# POWER_2_2.net
KiCad netlist of a schematic drawn in Altium Designer
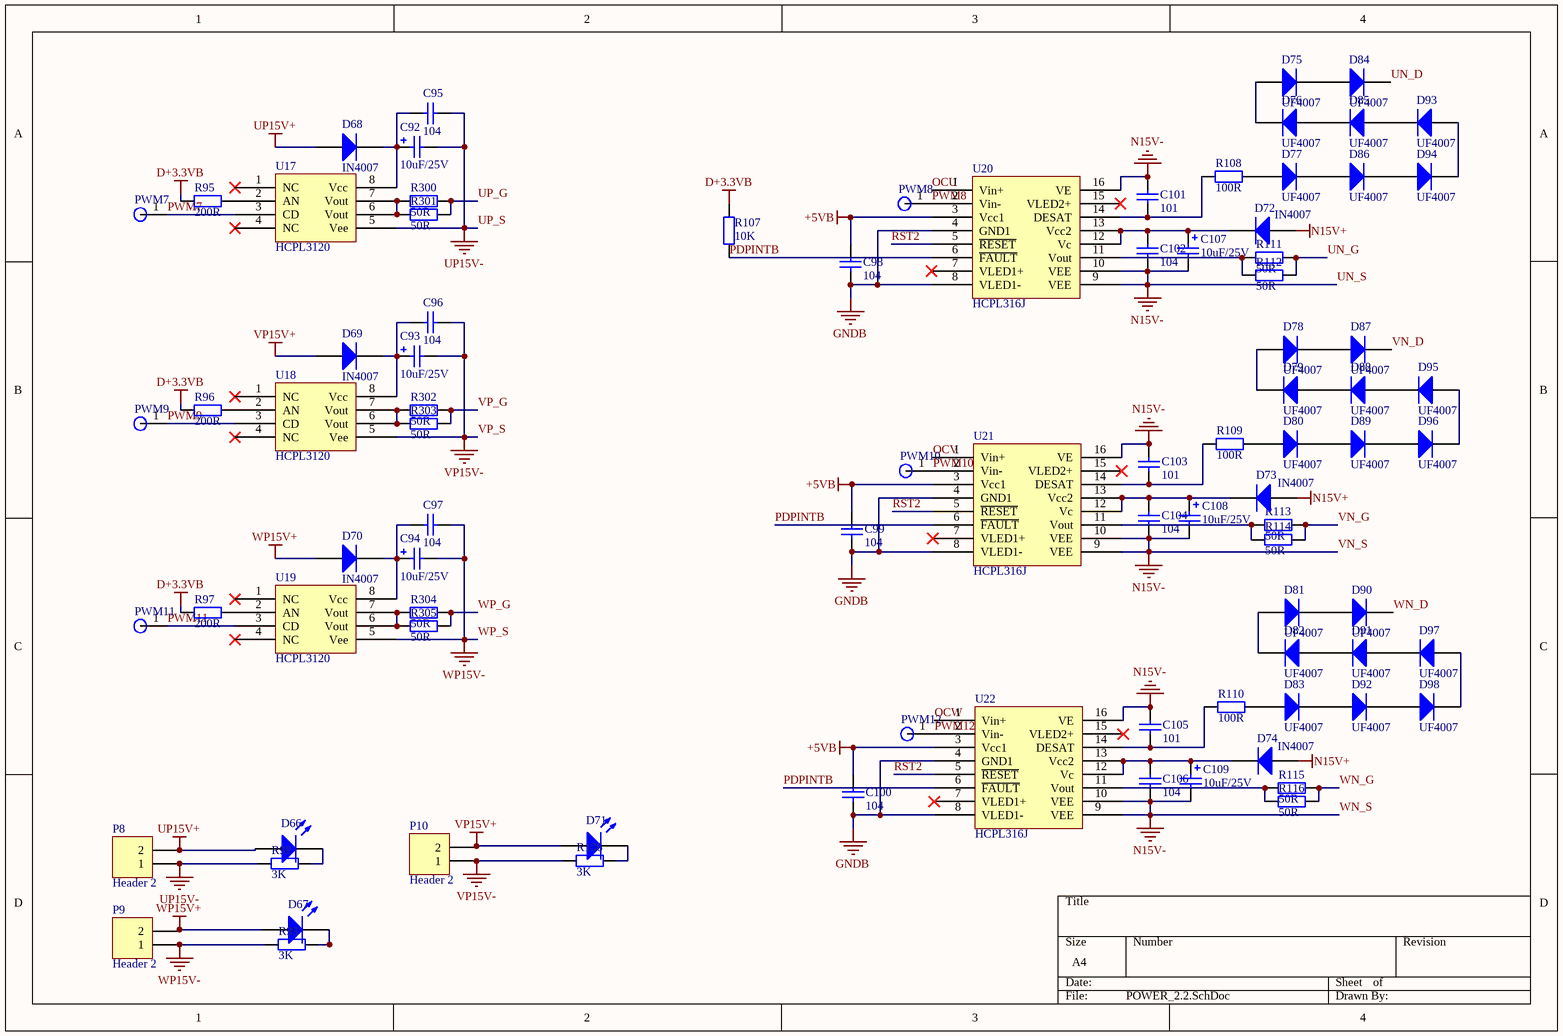
[diagram p0: POWER_2.2.SchDoc]

(export (version "E")
  (design (tool "Eeschema 10.0.6"))
  (components
    (comp (ref "C92")
      (value "10uF/25V")
      (footprint "C_10UF/25V")
      (description "钽电解")
      (libsource (lib "*") (part "Cap tan"))
    )
    (comp (ref "C93")
      (value "10uF/25V")
      (footprint "C_10UF/25V")
      (description "钽电解")
      (libsource (lib "*") (part "Cap tan"))
    )
    (comp (ref "C94")
      (value "10uF/25V")
      (footprint "C_10UF/25V")
      (description "钽电解")
      (libsource (lib "*") (part "Cap tan"))
    )
    (comp (ref "C95")
      (value "104")
      (footprint "C2012-0805")
      (description "普通电容")
      (libsource (lib "Mylib") (part "Cap"))
    )
    (comp (ref "C96")
      (value "104")
      (footprint "C2012-0805")
      (description "普通电容")
      (libsource (lib "Mylib") (part "Cap"))
    )
    (comp (ref "C97")
      (value "104")
      (footprint "C2012-0805")
      (description "普通电容")
      (libsource (lib "Mylib") (part "Cap"))
    )
    (comp (ref "C98")
      (value "104")
      (footprint "C2012-0805")
      (description "普通电容")
      (libsource (lib "*") (part "Cap"))
    )
    (comp (ref "C99")
      (value "104")
      (footprint "C2012-0805")
      (description "普通电容")
      (libsource (lib "*") (part "Cap"))
    )
    (comp (ref "C100")
      (value "104")
      (footprint "C2012-0805")
      (description "普通电容")
      (libsource (lib "*") (part "Cap"))
    )
    (comp (ref "C101")
      (value "101")
      (footprint "Rad-0.2")
      (description "普通电容")
      (libsource (lib "*") (part "Cap"))
    )
    (comp (ref "C102")
      (value "104")
      (footprint "C2012-0805")
      (description "普通电容")
      (libsource (lib "*") (part "Cap"))
    )
    (comp (ref "C103")
      (value "101")
      (footprint "Rad-0.2")
      (description "普通电容")
      (libsource (lib "*") (part "Cap"))
    )
    (comp (ref "C104")
      (value "104")
      (footprint "C2012-0805")
      (description "普通电容")
      (libsource (lib "*") (part "Cap"))
    )
    (comp (ref "C105")
      (value "101")
      (footprint "Rad-0.2")
      (description "普通电容")
      (libsource (lib "*") (part "Cap"))
    )
    (comp (ref "C106")
      (value "104")
      (footprint "C2012-0805")
      (description "普通电容")
      (libsource (lib "*") (part "Cap"))
    )
    (comp (ref "C107")
      (value "10uF/25V")
      (footprint "C_10UF/25V")
      (description "钽电解")
      (libsource (lib "*") (part "Cap tan"))
    )
    (comp (ref "C108")
      (value "10uF/25V")
      (footprint "C_10UF/25V")
      (description "钽电解")
      (libsource (lib "*") (part "Cap tan"))
    )
    (comp (ref "C109")
      (value "10uF/25V")
      (footprint "C_10UF/25V")
      (description "钽电解")
      (libsource (lib "*") (part "Cap tan"))
    )
    (comp (ref "D66") (value "~") (footprint "LED-SMD") (libsource (lib "Mylib") (part "LED")))
    (comp (ref "D67") (value "~") (footprint "LED-SMD") (libsource (lib "Mylib") (part "LED")))
    (comp (ref "D68")
      (value "IN4007")
      (footprint "DIODE4007")
      (description "普通整流二极管")
      (libsource (lib "Mylib") (part "Diode IN4007"))
    )
    (comp (ref "D69")
      (value "IN4007")
      (footprint "DIODE4007")
      (description "普通整流二极管")
      (libsource (lib "Mylib") (part "Diode IN4007"))
    )
    (comp (ref "D70")
      (value "IN4007")
      (footprint "DIODE4007")
      (description "普通整流二极管")
      (libsource (lib "Mylib") (part "Diode IN4007"))
    )
    (comp (ref "D71") (value "~") (footprint "LED-SMD") (libsource (lib "Mylib") (part "LED")))
    (comp (ref "D72")
      (value "IN4007")
      (footprint "DIODE4007")
      (description "普通整流二极管")
      (libsource (lib "*") (part "Diode IN4007"))
    )
    (comp (ref "D73")
      (value "IN4007")
      (footprint "DIODE4007")
      (description "普通整流二极管")
      (libsource (lib "*") (part "Diode IN4007"))
    )
    (comp (ref "D74")
      (value "IN4007")
      (footprint "DIODE4007")
      (description "普通整流二极管")
      (libsource (lib "*") (part "Diode IN4007"))
    )
    (comp (ref "D75")
      (value "UF4007")
      (footprint "DIODE4007")
      (description "普通整流二极管")
      (libsource (lib "*") (part "Diode IN4007"))
    )
    (comp (ref "D76")
      (value "UF4007")
      (footprint "DIODE4007")
      (description "普通整流二极管")
      (libsource (lib "*") (part "Diode IN4007"))
    )
    (comp (ref "D77")
      (value "UF4007")
      (footprint "DIODE4007")
      (description "普通整流二极管")
      (libsource (lib "*") (part "Diode IN4007"))
    )
    (comp (ref "D78")
      (value "UF4007")
      (footprint "DIODE4007")
      (description "普通整流二极管")
      (libsource (lib "*") (part "Diode IN4007"))
    )
    (comp (ref "D79")
      (value "UF4007")
      (footprint "DIODE4007")
      (description "普通整流二极管")
      (libsource (lib "*") (part "Diode IN4007"))
    )
    (comp (ref "D80")
      (value "UF4007")
      (footprint "DIODE4007")
      (description "普通整流二极管")
      (libsource (lib "*") (part "Diode IN4007"))
    )
    (comp (ref "D81")
      (value "UF4007")
      (footprint "DIODE4007")
      (description "普通整流二极管")
      (libsource (lib "*") (part "Diode IN4007"))
    )
    (comp (ref "D82")
      (value "UF4007")
      (footprint "DIODE4007")
      (description "普通整流二极管")
      (libsource (lib "*") (part "Diode IN4007"))
    )
    (comp (ref "D83")
      (value "UF4007")
      (footprint "DIODE4007")
      (description "普通整流二极管")
      (libsource (lib "*") (part "Diode IN4007"))
    )
    (comp (ref "D84")
      (value "UF4007")
      (footprint "DIODE4007")
      (description "普通整流二极管")
      (libsource (lib "*") (part "Diode IN4007"))
    )
    (comp (ref "D85")
      (value "UF4007")
      (footprint "DIODE4007")
      (description "普通整流二极管")
      (libsource (lib "*") (part "Diode IN4007"))
    )
    (comp (ref "D86")
      (value "UF4007")
      (footprint "DIODE4007")
      (description "普通整流二极管")
      (libsource (lib "*") (part "Diode IN4007"))
    )
    (comp (ref "D87")
      (value "UF4007")
      (footprint "DIODE4007")
      (description "普通整流二极管")
      (libsource (lib "*") (part "Diode IN4007"))
    )
    (comp (ref "D88")
      (value "UF4007")
      (footprint "DIODE4007")
      (description "普通整流二极管")
      (libsource (lib "*") (part "Diode IN4007"))
    )
    (comp (ref "D89")
      (value "UF4007")
      (footprint "DIODE4007")
      (description "普通整流二极管")
      (libsource (lib "*") (part "Diode IN4007"))
    )
    (comp (ref "D90")
      (value "UF4007")
      (footprint "DIODE4007")
      (description "普通整流二极管")
      (libsource (lib "*") (part "Diode IN4007"))
    )
    (comp (ref "D91")
      (value "UF4007")
      (footprint "DIODE4007")
      (description "普通整流二极管")
      (libsource (lib "*") (part "Diode IN4007"))
    )
    (comp (ref "D92")
      (value "UF4007")
      (footprint "DIODE4007")
      (description "普通整流二极管")
      (libsource (lib "*") (part "Diode IN4007"))
    )
    (comp (ref "D93")
      (value "UF4007")
      (footprint "DIODE4007")
      (description "普通整流二极管")
      (libsource (lib "*") (part "Diode IN4007"))
    )
    (comp (ref "D94")
      (value "UF4007")
      (footprint "DIODE4007")
      (description "普通整流二极管")
      (libsource (lib "*") (part "Diode IN4007"))
    )
    (comp (ref "D95")
      (value "UF4007")
      (footprint "DIODE4007")
      (description "普通整流二极管")
      (libsource (lib "*") (part "Diode IN4007"))
    )
    (comp (ref "D96")
      (value "UF4007")
      (footprint "DIODE4007")
      (description "普通整流二极管")
      (libsource (lib "*") (part "Diode IN4007"))
    )
    (comp (ref "D97")
      (value "UF4007")
      (footprint "DIODE4007")
      (description "普通整流二极管")
      (libsource (lib "*") (part "Diode IN4007"))
    )
    (comp (ref "D98")
      (value "UF4007")
      (footprint "DIODE4007")
      (description "普通整流二极管")
      (libsource (lib "*") (part "Diode IN4007"))
    )
    (comp (ref "P8")
      (value "Header 2")
      (footprint "HDR1X2")
      (description "Header, 2-Pin")
      (fields (field (name "PUBLISHER") "Altium Limited"))
      (libsource (lib "Miscellaneous Connectors") (part "Header 2"))
    )
    (comp (ref "P9")
      (value "Header 2")
      (footprint "HDR1X2")
      (description "Header, 2-Pin")
      (fields (field (name "PUBLISHER") "Altium Limited"))
      (libsource (lib "Miscellaneous Connectors") (part "Header 2"))
    )
    (comp (ref "P10")
      (value "Header 2")
      (footprint "HDR1X2")
      (description "Header, 2-Pin")
      (fields (field (name "PUBLISHER") "Altium Limited"))
      (libsource (lib "Miscellaneous Connectors") (part "Header 2"))
    )
    (comp (ref "R95") (value "200R") (footprint "R2012-0805") (libsource (lib "*") (part "Res")))
    (comp (ref "R96") (value "200R") (footprint "R2012-0805") (libsource (lib "*") (part "Res")))
    (comp (ref "R97") (value "200R") (footprint "R2012-0805") (libsource (lib "*") (part "Res")))
    (comp (ref "R98") (value "3K") (footprint "R2012-0805") (libsource (lib "") (part "Res_1")))
    (comp (ref "R99") (value "3K") (footprint "R2012-0805") (libsource (lib "") (part "Res_1")))
    (comp (ref "R106") (value "3K") (footprint "R2012-0805") (libsource (lib "") (part "Res_1")))
    (comp (ref "R107") (value "10K") (footprint "R2012-0805") (libsource (lib "") (part "Res_2")))
    (comp (ref "R108") (value "100R") (footprint "R2012-0805") (libsource (lib "*") (part "Res")))
    (comp (ref "R109") (value "100R") (footprint "R2012-0805") (libsource (lib "*") (part "Res")))
    (comp (ref "R110") (value "100R") (footprint "R2012-0805") (libsource (lib "*") (part "Res")))
    (comp (ref "R111") (value "50R") (footprint "R2012-0805") (libsource (lib "*") (part "Res")))
    (comp (ref "R112") (value "50R") (footprint "R2012-0805") (libsource (lib "*") (part "Res")))
    (comp (ref "R113") (value "50R") (footprint "R2012-0805") (libsource (lib "*") (part "Res")))
    (comp (ref "R114") (value "50R") (footprint "R2012-0805") (libsource (lib "*") (part "Res")))
    (comp (ref "R115") (value "50R") (footprint "R2012-0805") (libsource (lib "*") (part "Res")))
    (comp (ref "R116") (value "50R") (footprint "R2012-0805") (libsource (lib "*") (part "Res")))
    (comp (ref "R300") (value "50R") (footprint "R2012-0805") (libsource (lib "*") (part "Res")))
    (comp (ref "R301") (value "50R") (footprint "R2012-0805") (libsource (lib "*") (part "Res")))
    (comp (ref "R302") (value "50R") (footprint "R2012-0805") (libsource (lib "*") (part "Res")))
    (comp (ref "R303") (value "50R") (footprint "R2012-0805") (libsource (lib "*") (part "Res")))
    (comp (ref "R304") (value "50R") (footprint "R2012-0805") (libsource (lib "*") (part "Res")))
    (comp (ref "R305") (value "50R") (footprint "R2012-0805") (libsource (lib "*") (part "Res")))
    (comp (ref "T32") (value "PWM8") (footprint "PIN1") (description "测试脚") (libsource (lib "*") (part "TP")))
    (comp (ref "T33")
      (value "PWM10")
      (footprint "PIN1")
      (description "测试脚")
      (libsource (lib "*") (part "TP"))
    )
    (comp (ref "T34")
      (value "PWM12")
      (footprint "PIN1")
      (description "测试脚")
      (libsource (lib "*") (part "TP"))
    )
    (comp (ref "TP6")
      (value "PWM7")
      (footprint "PIN1")
      (description "测试脚")
      (libsource (lib "Mylib") (part "TP"))
    )
    (comp (ref "TP7")
      (value "PWM9")
      (footprint "PIN1")
      (description "测试脚")
      (libsource (lib "Mylib") (part "TP"))
    )
    (comp (ref "TP8")
      (value "PWM11")
      (footprint "PIN1")
      (description "测试脚")
      (libsource (lib "Mylib") (part "TP"))
    )
    (comp (ref "U17") (value "HCPL3120") (footprint "HCPL3120") (libsource (lib "Mylib") (part "HCPL3120")))
    (comp (ref "U18") (value "HCPL3120") (footprint "HCPL3120") (libsource (lib "Mylib") (part "HCPL3120")))
    (comp (ref "U19") (value "HCPL3120") (footprint "HCPL3120") (libsource (lib "Mylib") (part "HCPL3120")))
    (comp (ref "U20") (value "HCPL316J") (footprint "HCPL316J") (libsource (lib "*") (part "HCPL316J")))
    (comp (ref "U21") (value "HCPL316J") (footprint "HCPL316J") (libsource (lib "*") (part "HCPL316J")))
    (comp (ref "U22") (value "HCPL316J") (footprint "HCPL316J") (libsource (lib "*") (part "HCPL316J")))
  )
  (nets
    (net (code "1") (name "+5VB") (class "Default")
      (node (ref "C100") (pin "2") (pinfunction "2_2") (pintype "passive"))
      (node (ref "C98") (pin "2") (pinfunction "2_2") (pintype "passive"))
      (node (ref "C99") (pin "2") (pinfunction "2_2") (pintype "passive"))
      (node (ref "U20") (pin "3") (pinfunction "Vcc1_3") (pintype "passive"))
      (node (ref "U21") (pin "3") (pinfunction "Vcc1_3") (pintype "passive"))
      (node (ref "U22") (pin "3") (pinfunction "Vcc1_3") (pintype "passive"))
    )
    (net (code "2") (name "/OCU") (class "Default")
      (node (ref "U20") (pin "1") (pinfunction "Vin+_1") (pintype "passive"))
    )
    (net (code "3") (name "/OCV") (class "Default")
      (node (ref "U21") (pin "1") (pinfunction "Vin+_1") (pintype "passive"))
    )
    (net (code "4") (name "/OCW") (class "Default")
      (node (ref "U22") (pin "1") (pinfunction "Vin+_1") (pintype "passive"))
    )
    (net (code "5") (name "/PDPINTB") (class "Default")
      (node (ref "R107") (pin "1") (pinfunction "1_1") (pintype "passive"))
      (node (ref "U20") (pin "6") (pinfunction "~{FAULT}_6") (pintype "passive"))
      (node (ref "U21") (pin "6") (pinfunction "~{FAULT}_6") (pintype "passive"))
      (node (ref "U22") (pin "6") (pinfunction "~{FAULT}_6") (pintype "passive"))
    )
    (net (code "6") (name "/PWM7") (class "Default")
      (node (ref "TP6") (pin "1") (pinfunction "A_1") (pintype "passive"))
      (node (ref "U17") (pin "3") (pinfunction "CD_3") (pintype "passive"))
    )
    (net (code "7") (name "/PWM8") (class "Default")
      (node (ref "T32") (pin "1") (pinfunction "A_1") (pintype "passive"))
      (node (ref "U20") (pin "2") (pinfunction "Vin-_2") (pintype "passive"))
    )
    (net (code "8") (name "/PWM9") (class "Default")
      (node (ref "TP7") (pin "1") (pinfunction "A_1") (pintype "passive"))
      (node (ref "U18") (pin "3") (pinfunction "CD_3") (pintype "passive"))
    )
    (net (code "9") (name "/PWM10") (class "Default")
      (node (ref "T33") (pin "1") (pinfunction "A_1") (pintype "passive"))
      (node (ref "U21") (pin "2") (pinfunction "Vin-_2") (pintype "passive"))
    )
    (net (code "10") (name "/PWM11") (class "Default")
      (node (ref "TP8") (pin "1") (pinfunction "A_1") (pintype "passive"))
      (node (ref "U19") (pin "3") (pinfunction "CD_3") (pintype "passive"))
    )
    (net (code "11") (name "/PWM12") (class "Default")
      (node (ref "T34") (pin "1") (pinfunction "A_1") (pintype "passive"))
      (node (ref "U22") (pin "2") (pinfunction "Vin-_2") (pintype "passive"))
    )
    (net (code "12") (name "/RST2") (class "Default")
      (node (ref "U20") (pin "5") (pinfunction "~{RESET}_5") (pintype "passive"))
      (node (ref "U21") (pin "5") (pinfunction "~{RESET}_5") (pintype "passive"))
      (node (ref "U22") (pin "5") (pinfunction "~{RESET}_5") (pintype "passive"))
    )
    (net (code "13") (name "/UN_D") (class "Default")
      (node (ref "D84") (pin "2") (pinfunction "K_2") (pintype "passive"))
    )
    (net (code "14") (name "/UN_G") (class "Default")
      (node (ref "R111") (pin "1") (pinfunction "1_1") (pintype "passive"))
      (node (ref "R112") (pin "1") (pinfunction "1_1") (pintype "passive"))
    )
    (net (code "15") (name "/UP_G") (class "Default")
      (node (ref "R300") (pin "1") (pinfunction "1_1") (pintype "passive"))
      (node (ref "R301") (pin "1") (pinfunction "1_1") (pintype "passive"))
    )
    (net (code "16") (name "/VN_D") (class "Default")
      (node (ref "D87") (pin "2") (pinfunction "K_2") (pintype "passive"))
    )
    (net (code "17") (name "/VN_G") (class "Default")
      (node (ref "R113") (pin "1") (pinfunction "1_1") (pintype "passive"))
      (node (ref "R114") (pin "1") (pinfunction "1_1") (pintype "passive"))
    )
    (net (code "18") (name "/VP_G") (class "Default")
      (node (ref "R302") (pin "1") (pinfunction "1_1") (pintype "passive"))
      (node (ref "R303") (pin "1") (pinfunction "1_1") (pintype "passive"))
    )
    (net (code "19") (name "/WN_D") (class "Default")
      (node (ref "D90") (pin "2") (pinfunction "K_2") (pintype "passive"))
    )
    (net (code "20") (name "/WN_G") (class "Default")
      (node (ref "R115") (pin "1") (pinfunction "1_1") (pintype "passive"))
      (node (ref "R116") (pin "1") (pinfunction "1_1") (pintype "passive"))
    )
    (net (code "21") (name "/WP_G") (class "Default")
      (node (ref "R304") (pin "1") (pinfunction "1_1") (pintype "passive"))
      (node (ref "R305") (pin "1") (pinfunction "1_1") (pintype "passive"))
    )
    (net (code "22") (name "D+3.3VB") (class "Default")
      (node (ref "R107") (pin "2") (pinfunction "2_2") (pintype "passive"))
      (node (ref "R95") (pin "2") (pinfunction "2_2") (pintype "passive"))
      (node (ref "R96") (pin "2") (pinfunction "2_2") (pintype "passive"))
      (node (ref "R97") (pin "2") (pinfunction "2_2") (pintype "passive"))
    )
    (net (code "23") (name "GNDB") (class "Default")
      (node (ref "C100") (pin "1") (pinfunction "1_1") (pintype "passive"))
      (node (ref "C98") (pin "1") (pinfunction "1_1") (pintype "passive"))
      (node (ref "C99") (pin "1") (pinfunction "1_1") (pintype "passive"))
      (node (ref "U20") (pin "4") (pinfunction "GND1_4") (pintype "passive"))
      (node (ref "U20") (pin "8") (pinfunction "VLED1-_8") (pintype "passive"))
      (node (ref "U21") (pin "4") (pinfunction "GND1_4") (pintype "passive"))
      (node (ref "U21") (pin "8") (pinfunction "VLED1-_8") (pintype "passive"))
      (node (ref "U22") (pin "4") (pinfunction "GND1_4") (pintype "passive"))
      (node (ref "U22") (pin "8") (pinfunction "VLED1-_8") (pintype "passive"))
    )
    (net (code "24") (name "N15V+") (class "Default")
      (node (ref "D72") (pin "1") (pinfunction "A_1") (pintype "passive"))
      (node (ref "D73") (pin "1") (pinfunction "A_1") (pintype "passive"))
      (node (ref "D74") (pin "1") (pinfunction "A_1") (pintype "passive"))
    )
    (net (code "25") (name "N15V-") (class "Default")
      (node (ref "C101") (pin "2") (pinfunction "2_2") (pintype "passive"))
      (node (ref "C102") (pin "1") (pinfunction "1_1") (pintype "passive"))
      (node (ref "C103") (pin "2") (pinfunction "2_2") (pintype "passive"))
      (node (ref "C104") (pin "1") (pinfunction "1_1") (pintype "passive"))
      (node (ref "C105") (pin "2") (pinfunction "2_2") (pintype "passive"))
      (node (ref "C106") (pin "1") (pinfunction "1_1") (pintype "passive"))
      (node (ref "C107") (pin "2") (pinfunction "2_2") (pintype "passive"))
      (node (ref "C108") (pin "2") (pinfunction "2_2") (pintype "passive"))
      (node (ref "C109") (pin "2") (pinfunction "2_2") (pintype "passive"))
      (node (ref "U20") (pin "10") (pinfunction "VEE_10") (pintype "passive"))
      (node (ref "U20") (pin "16") (pinfunction "VE_16") (pintype "passive"))
      (node (ref "U20") (pin "9") (pinfunction "VEE_9") (pintype "passive"))
      (node (ref "U21") (pin "10") (pinfunction "VEE_10") (pintype "passive"))
      (node (ref "U21") (pin "16") (pinfunction "VE_16") (pintype "passive"))
      (node (ref "U21") (pin "9") (pinfunction "VEE_9") (pintype "passive"))
      (node (ref "U22") (pin "10") (pinfunction "VEE_10") (pintype "passive"))
      (node (ref "U22") (pin "16") (pinfunction "VE_16") (pintype "passive"))
      (node (ref "U22") (pin "9") (pinfunction "VEE_9") (pintype "passive"))
    )
    (net (code "26") (name "Net-(D66-K)") (class "Default")
      (node (ref "D66") (pin "2") (pinfunction "K_2") (pintype "passive"))
      (node (ref "R98") (pin "2") (pinfunction "2_2") (pintype "passive"))
    )
    (net (code "27") (name "Net-(D67-K)") (class "Default")
      (node (ref "D67") (pin "2") (pinfunction "K_2") (pintype "passive"))
      (node (ref "R99") (pin "2") (pinfunction "2_2") (pintype "passive"))
    )
    (net (code "28") (name "Net-(D68-K)") (class "Default")
      (node (ref "C92") (pin "1") (pinfunction "1_1") (pintype "passive"))
      (node (ref "C95") (pin "1") (pinfunction "1_1") (pintype "passive"))
      (node (ref "D68") (pin "2") (pinfunction "K_2") (pintype "passive"))
      (node (ref "U17") (pin "8") (pinfunction "Vcc_8") (pintype "passive"))
    )
    (net (code "29") (name "Net-(D69-K)") (class "Default")
      (node (ref "C93") (pin "1") (pinfunction "1_1") (pintype "passive"))
      (node (ref "C96") (pin "1") (pinfunction "1_1") (pintype "passive"))
      (node (ref "D69") (pin "2") (pinfunction "K_2") (pintype "passive"))
      (node (ref "U18") (pin "8") (pinfunction "Vcc_8") (pintype "passive"))
    )
    (net (code "30") (name "Net-(D70-K)") (class "Default")
      (node (ref "C94") (pin "1") (pinfunction "1_1") (pintype "passive"))
      (node (ref "C97") (pin "1") (pinfunction "1_1") (pintype "passive"))
      (node (ref "D70") (pin "2") (pinfunction "K_2") (pintype "passive"))
      (node (ref "U19") (pin "8") (pinfunction "Vcc_8") (pintype "passive"))
    )
    (net (code "31") (name "Net-(D71-K)") (class "Default")
      (node (ref "D71") (pin "2") (pinfunction "K_2") (pintype "passive"))
      (node (ref "R106") (pin "2") (pinfunction "2_2") (pintype "passive"))
    )
    (net (code "32") (name "Net-(D72-K)") (class "Default")
      (node (ref "C102") (pin "2") (pinfunction "2_2") (pintype "passive"))
      (node (ref "C107") (pin "1") (pinfunction "1_1") (pintype "passive"))
      (node (ref "D72") (pin "2") (pinfunction "K_2") (pintype "passive"))
      (node (ref "U20") (pin "12") (pinfunction "Vc_12") (pintype "passive"))
      (node (ref "U20") (pin "13") (pinfunction "Vcc2_13") (pintype "passive"))
    )
    (net (code "33") (name "Net-(D73-K)") (class "Default")
      (node (ref "C104") (pin "2") (pinfunction "2_2") (pintype "passive"))
      (node (ref "C108") (pin "1") (pinfunction "1_1") (pintype "passive"))
      (node (ref "D73") (pin "2") (pinfunction "K_2") (pintype "passive"))
      (node (ref "U21") (pin "12") (pinfunction "Vc_12") (pintype "passive"))
      (node (ref "U21") (pin "13") (pinfunction "Vcc2_13") (pintype "passive"))
    )
    (net (code "34") (name "Net-(D74-K)") (class "Default")
      (node (ref "C106") (pin "2") (pinfunction "2_2") (pintype "passive"))
      (node (ref "C109") (pin "1") (pinfunction "1_1") (pintype "passive"))
      (node (ref "D74") (pin "2") (pinfunction "K_2") (pintype "passive"))
      (node (ref "U22") (pin "12") (pinfunction "Vc_12") (pintype "passive"))
      (node (ref "U22") (pin "13") (pinfunction "Vcc2_13") (pintype "passive"))
    )
    (net (code "35") (name "Net-(D75-A)") (class "Default")
      (node (ref "D75") (pin "1") (pinfunction "A_1") (pintype "passive"))
      (node (ref "D76") (pin "2") (pinfunction "K_2") (pintype "passive"))
    )
    (net (code "36") (name "Net-(D75-K)") (class "Default")
      (node (ref "D75") (pin "2") (pinfunction "K_2") (pintype "passive"))
      (node (ref "D84") (pin "1") (pinfunction "A_1") (pintype "passive"))
    )
    (net (code "37") (name "Net-(D76-A)") (class "Default")
      (node (ref "D76") (pin "1") (pinfunction "A_1") (pintype "passive"))
      (node (ref "D85") (pin "2") (pinfunction "K_2") (pintype "passive"))
    )
    (net (code "38") (name "Net-(D77-A)") (class "Default")
      (node (ref "D77") (pin "1") (pinfunction "A_1") (pintype "passive"))
      (node (ref "R108") (pin "1") (pinfunction "1_1") (pintype "passive"))
    )
    (net (code "39") (name "Net-(D77-K)") (class "Default")
      (node (ref "D77") (pin "2") (pinfunction "K_2") (pintype "passive"))
      (node (ref "D86") (pin "1") (pinfunction "A_1") (pintype "passive"))
    )
    (net (code "40") (name "Net-(D78-A)") (class "Default")
      (node (ref "D78") (pin "1") (pinfunction "A_1") (pintype "passive"))
      (node (ref "D79") (pin "2") (pinfunction "K_2") (pintype "passive"))
    )
    (net (code "41") (name "Net-(D78-K)") (class "Default")
      (node (ref "D78") (pin "2") (pinfunction "K_2") (pintype "passive"))
      (node (ref "D87") (pin "1") (pinfunction "A_1") (pintype "passive"))
    )
    (net (code "42") (name "Net-(D79-A)") (class "Default")
      (node (ref "D79") (pin "1") (pinfunction "A_1") (pintype "passive"))
      (node (ref "D88") (pin "2") (pinfunction "K_2") (pintype "passive"))
    )
    (net (code "43") (name "Net-(D80-A)") (class "Default")
      (node (ref "D80") (pin "1") (pinfunction "A_1") (pintype "passive"))
      (node (ref "R109") (pin "1") (pinfunction "1_1") (pintype "passive"))
    )
    (net (code "44") (name "Net-(D80-K)") (class "Default")
      (node (ref "D80") (pin "2") (pinfunction "K_2") (pintype "passive"))
      (node (ref "D89") (pin "1") (pinfunction "A_1") (pintype "passive"))
    )
    (net (code "45") (name "Net-(D81-A)") (class "Default")
      (node (ref "D81") (pin "1") (pinfunction "A_1") (pintype "passive"))
      (node (ref "D82") (pin "2") (pinfunction "K_2") (pintype "passive"))
    )
    (net (code "46") (name "Net-(D81-K)") (class "Default")
      (node (ref "D81") (pin "2") (pinfunction "K_2") (pintype "passive"))
      (node (ref "D90") (pin "1") (pinfunction "A_1") (pintype "passive"))
    )
    (net (code "47") (name "Net-(D82-A)") (class "Default")
      (node (ref "D82") (pin "1") (pinfunction "A_1") (pintype "passive"))
      (node (ref "D91") (pin "2") (pinfunction "K_2") (pintype "passive"))
    )
    (net (code "48") (name "Net-(D83-A)") (class "Default")
      (node (ref "D83") (pin "1") (pinfunction "A_1") (pintype "passive"))
      (node (ref "R110") (pin "1") (pinfunction "1_1") (pintype "passive"))
    )
    (net (code "49") (name "Net-(D83-K)") (class "Default")
      (node (ref "D83") (pin "2") (pinfunction "K_2") (pintype "passive"))
      (node (ref "D92") (pin "1") (pinfunction "A_1") (pintype "passive"))
    )
    (net (code "50") (name "Net-(D85-A)") (class "Default")
      (node (ref "D85") (pin "1") (pinfunction "A_1") (pintype "passive"))
      (node (ref "D93") (pin "2") (pinfunction "K_2") (pintype "passive"))
    )
    (net (code "51") (name "Net-(D86-K)") (class "Default")
      (node (ref "D86") (pin "2") (pinfunction "K_2") (pintype "passive"))
      (node (ref "D94") (pin "1") (pinfunction "A_1") (pintype "passive"))
    )
    (net (code "52") (name "Net-(D88-A)") (class "Default")
      (node (ref "D88") (pin "1") (pinfunction "A_1") (pintype "passive"))
      (node (ref "D95") (pin "2") (pinfunction "K_2") (pintype "passive"))
    )
    (net (code "53") (name "Net-(D89-K)") (class "Default")
      (node (ref "D89") (pin "2") (pinfunction "K_2") (pintype "passive"))
      (node (ref "D96") (pin "1") (pinfunction "A_1") (pintype "passive"))
    )
    (net (code "54") (name "Net-(D91-A)") (class "Default")
      (node (ref "D91") (pin "1") (pinfunction "A_1") (pintype "passive"))
      (node (ref "D97") (pin "2") (pinfunction "K_2") (pintype "passive"))
    )
    (net (code "55") (name "Net-(D92-K)") (class "Default")
      (node (ref "D92") (pin "2") (pinfunction "K_2") (pintype "passive"))
      (node (ref "D98") (pin "1") (pinfunction "A_1") (pintype "passive"))
    )
    (net (code "56") (name "Net-(D93-A)") (class "Default")
      (node (ref "D93") (pin "1") (pinfunction "A_1") (pintype "passive"))
      (node (ref "D94") (pin "2") (pinfunction "K_2") (pintype "passive"))
    )
    (net (code "57") (name "Net-(D95-A)") (class "Default")
      (node (ref "D95") (pin "1") (pinfunction "A_1") (pintype "passive"))
      (node (ref "D96") (pin "2") (pinfunction "K_2") (pintype "passive"))
    )
    (net (code "58") (name "Net-(D97-A)") (class "Default")
      (node (ref "D97") (pin "1") (pinfunction "A_1") (pintype "passive"))
      (node (ref "D98") (pin "2") (pinfunction "K_2") (pintype "passive"))
    )
    (net (code "59") (name "Net-(R300-Pad2)") (class "Default")
      (node (ref "R300") (pin "2") (pinfunction "2_2") (pintype "passive"))
      (node (ref "R301") (pin "2") (pinfunction "2_2") (pintype "passive"))
      (node (ref "U17") (pin "6") (pinfunction "Vout_6") (pintype "passive"))
      (node (ref "U17") (pin "7") (pinfunction "Vout_7") (pintype "passive"))
    )
    (net (code "60") (name "Net-(R302-Pad2)") (class "Default")
      (node (ref "R302") (pin "2") (pinfunction "2_2") (pintype "passive"))
      (node (ref "R303") (pin "2") (pinfunction "2_2") (pintype "passive"))
      (node (ref "U18") (pin "6") (pinfunction "Vout_6") (pintype "passive"))
      (node (ref "U18") (pin "7") (pinfunction "Vout_7") (pintype "passive"))
    )
    (net (code "61") (name "Net-(R304-Pad2)") (class "Default")
      (node (ref "R304") (pin "2") (pinfunction "2_2") (pintype "passive"))
      (node (ref "R305") (pin "2") (pinfunction "2_2") (pintype "passive"))
      (node (ref "U19") (pin "6") (pinfunction "Vout_6") (pintype "passive"))
      (node (ref "U19") (pin "7") (pinfunction "Vout_7") (pintype "passive"))
    )
    (net (code "62") (name "Net-(U17-AN)") (class "Default")
      (node (ref "R95") (pin "1") (pinfunction "1_1") (pintype "passive"))
      (node (ref "U17") (pin "2") (pinfunction "AN_2") (pintype "passive"))
    )
    (net (code "63") (name "Net-(U18-AN)") (class "Default")
      (node (ref "R96") (pin "1") (pinfunction "1_1") (pintype "passive"))
      (node (ref "U18") (pin "2") (pinfunction "AN_2") (pintype "passive"))
    )
    (net (code "64") (name "Net-(U19-AN)") (class "Default")
      (node (ref "R97") (pin "1") (pinfunction "1_1") (pintype "passive"))
      (node (ref "U19") (pin "2") (pinfunction "AN_2") (pintype "passive"))
    )
    (net (code "65") (name "Net-(U20-DESAT)") (class "Default")
      (node (ref "C101") (pin "1") (pinfunction "1_1") (pintype "passive"))
      (node (ref "R108") (pin "2") (pinfunction "2_2") (pintype "passive"))
      (node (ref "U20") (pin "14") (pinfunction "DESAT_14") (pintype "passive"))
    )
    (net (code "66") (name "Net-(U20-Vout)") (class "Default")
      (node (ref "R111") (pin "2") (pinfunction "2_2") (pintype "passive"))
      (node (ref "R112") (pin "2") (pinfunction "2_2") (pintype "passive"))
      (node (ref "U20") (pin "11") (pinfunction "Vout_11") (pintype "passive"))
    )
    (net (code "67") (name "Net-(U21-DESAT)") (class "Default")
      (node (ref "C103") (pin "1") (pinfunction "1_1") (pintype "passive"))
      (node (ref "R109") (pin "2") (pinfunction "2_2") (pintype "passive"))
      (node (ref "U21") (pin "14") (pinfunction "DESAT_14") (pintype "passive"))
    )
    (net (code "68") (name "Net-(U21-Vout)") (class "Default")
      (node (ref "R113") (pin "2") (pinfunction "2_2") (pintype "passive"))
      (node (ref "R114") (pin "2") (pinfunction "2_2") (pintype "passive"))
      (node (ref "U21") (pin "11") (pinfunction "Vout_11") (pintype "passive"))
    )
    (net (code "69") (name "Net-(U22-DESAT)") (class "Default")
      (node (ref "C105") (pin "1") (pinfunction "1_1") (pintype "passive"))
      (node (ref "R110") (pin "2") (pinfunction "2_2") (pintype "passive"))
      (node (ref "U22") (pin "14") (pinfunction "DESAT_14") (pintype "passive"))
    )
    (net (code "70") (name "Net-(U22-Vout)") (class "Default")
      (node (ref "R115") (pin "2") (pinfunction "2_2") (pintype "passive"))
      (node (ref "R116") (pin "2") (pinfunction "2_2") (pintype "passive"))
      (node (ref "U22") (pin "11") (pinfunction "Vout_11") (pintype "passive"))
    )
    (net (code "71") (name "UP15V+") (class "Default")
      (node (ref "D66") (pin "1") (pinfunction "A_1") (pintype "passive"))
      (node (ref "D68") (pin "1") (pinfunction "A_1") (pintype "passive"))
      (node (ref "P8") (pin "2") (pinfunction "2_2") (pintype "passive"))
    )
    (net (code "72") (name "UP15V-") (class "Default")
      (node (ref "C92") (pin "2") (pinfunction "2_2") (pintype "passive"))
      (node (ref "C95") (pin "2") (pinfunction "2_2") (pintype "passive"))
      (node (ref "P8") (pin "1") (pinfunction "1_1") (pintype "passive"))
      (node (ref "R98") (pin "1") (pinfunction "1_1") (pintype "passive"))
      (node (ref "U17") (pin "5") (pinfunction "Vee_5") (pintype "passive"))
    )
    (net (code "73") (name "VP15V+") (class "Default")
      (node (ref "D69") (pin "1") (pinfunction "A_1") (pintype "passive"))
      (node (ref "D71") (pin "1") (pinfunction "A_1") (pintype "passive"))
      (node (ref "P10") (pin "2") (pinfunction "2_2") (pintype "passive"))
    )
    (net (code "74") (name "VP15V-") (class "Default")
      (node (ref "C93") (pin "2") (pinfunction "2_2") (pintype "passive"))
      (node (ref "C96") (pin "2") (pinfunction "2_2") (pintype "passive"))
      (node (ref "P10") (pin "1") (pinfunction "1_1") (pintype "passive"))
      (node (ref "R106") (pin "1") (pinfunction "1_1") (pintype "passive"))
      (node (ref "U18") (pin "5") (pinfunction "Vee_5") (pintype "passive"))
    )
    (net (code "75") (name "WP15V+") (class "Default")
      (node (ref "D67") (pin "1") (pinfunction "A_1") (pintype "passive"))
      (node (ref "D70") (pin "1") (pinfunction "A_1") (pintype "passive"))
      (node (ref "P9") (pin "2") (pinfunction "2_2") (pintype "passive"))
    )
    (net (code "76") (name "WP15V-") (class "Default")
      (node (ref "C94") (pin "2") (pinfunction "2_2") (pintype "passive"))
      (node (ref "C97") (pin "2") (pinfunction "2_2") (pintype "passive"))
      (node (ref "P9") (pin "1") (pinfunction "1_1") (pintype "passive"))
      (node (ref "R99") (pin "1") (pinfunction "1_1") (pintype "passive"))
      (node (ref "U19") (pin "5") (pinfunction "Vee_5") (pintype "passive"))
    )
    (net (code "77") (name "unconnected-(U17-NC-Pad1)") (class "Default")
      (node (ref "U17") (pin "1") (pinfunction "NC_1") (pintype "passive+no_connect"))
    )
    (net (code "78") (name "unconnected-(U17-NC-Pad4)") (class "Default")
      (node (ref "U17") (pin "4") (pinfunction "NC_4") (pintype "passive+no_connect"))
    )
    (net (code "79") (name "unconnected-(U18-NC-Pad1)") (class "Default")
      (node (ref "U18") (pin "1") (pinfunction "NC_1") (pintype "passive+no_connect"))
    )
    (net (code "80") (name "unconnected-(U18-NC-Pad4)") (class "Default")
      (node (ref "U18") (pin "4") (pinfunction "NC_4") (pintype "passive+no_connect"))
    )
    (net (code "81") (name "unconnected-(U19-NC-Pad1)") (class "Default")
      (node (ref "U19") (pin "1") (pinfunction "NC_1") (pintype "passive+no_connect"))
    )
    (net (code "82") (name "unconnected-(U19-NC-Pad4)") (class "Default")
      (node (ref "U19") (pin "4") (pinfunction "NC_4") (pintype "passive+no_connect"))
    )
    (net (code "83") (name "unconnected-(U20-VLED1+-Pad7)") (class "Default")
      (node (ref "U20") (pin "7") (pinfunction "VLED1+_7") (pintype "passive+no_connect"))
    )
    (net (code "84") (name "unconnected-(U20-VLED2+-Pad15)") (class "Default")
      (node (ref "U20") (pin "15") (pinfunction "VLED2+_15") (pintype "passive+no_connect"))
    )
    (net (code "85") (name "unconnected-(U21-VLED1+-Pad7)") (class "Default")
      (node (ref "U21") (pin "7") (pinfunction "VLED1+_7") (pintype "passive+no_connect"))
    )
    (net (code "86") (name "unconnected-(U21-VLED2+-Pad15)") (class "Default")
      (node (ref "U21") (pin "15") (pinfunction "VLED2+_15") (pintype "passive+no_connect"))
    )
    (net (code "87") (name "unconnected-(U22-VLED1+-Pad7)") (class "Default")
      (node (ref "U22") (pin "7") (pinfunction "VLED1+_7") (pintype "passive+no_connect"))
    )
    (net (code "88") (name "unconnected-(U22-VLED2+-Pad15)") (class "Default")
      (node (ref "U22") (pin "15") (pinfunction "VLED2+_15") (pintype "passive+no_connect"))
    )
  )
)
